# MegaShield_v0_6.net
KiCad netlist of a schematic drawn in EAGLE
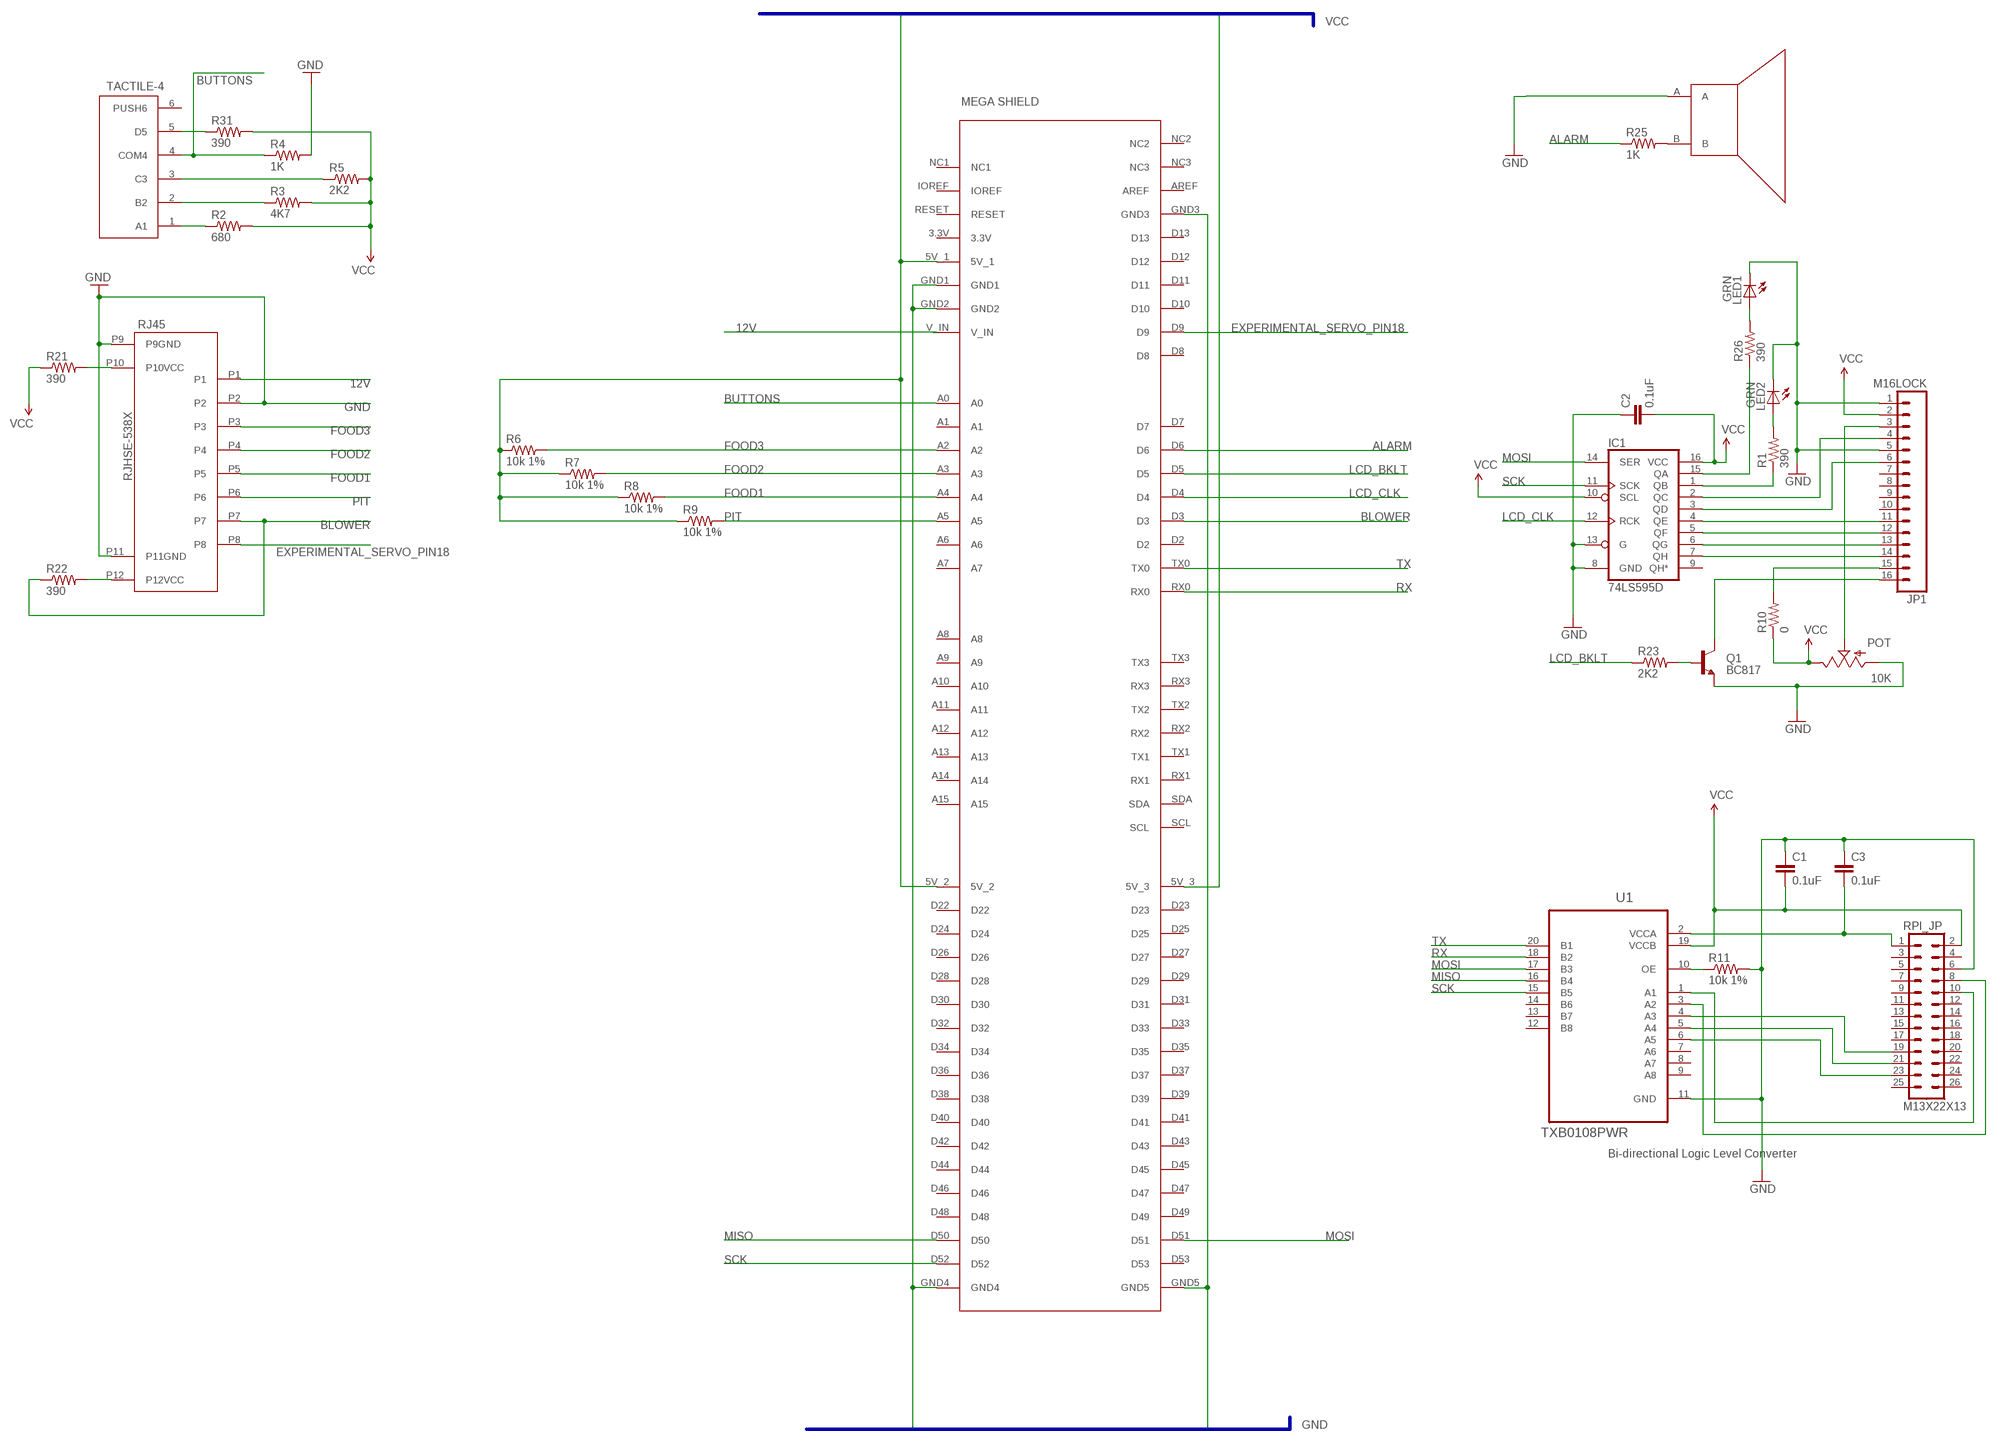
[diagram p0: schematic, sheet 1]

(export (version "E")
  (design (tool "Eeschema 10.0.6"))
  (components
    (comp (ref "C1")
      (value "0.1uF")
      (footprint "eagle-import:0805")
      (libsource (lib "eagle-import") (part "SparkFun-Passives_CAP0805"))
    )
    (comp (ref "C2")
      (value "0.1uF")
      (footprint "eagle-import:0805")
      (libsource (lib "eagle-import") (part "CAP0805"))
    )
    (comp (ref "C3")
      (value "0.1uF")
      (footprint "eagle-import:0805")
      (libsource (lib "eagle-import") (part "SparkFun-Passives_CAP0805"))
    )
    (comp (ref "IC1")
      (value "74LS595D")
      (footprint "eagle-import:SO16")
      (libsource (lib "eagle-import") (part "74595DLS"))
    )
    (comp (ref "JP1")
      (value "M16LOCK")
      (footprint "eagle-import:1X16_LOCK")
      (libsource (lib "eagle-import") (part "M16LOCK"))
    )
    (comp (ref "LED1")
      (value "GRN")
      (footprint "eagle-import:LED5MM")
      (libsource (lib "eagle-import") (part "LED5MM"))
    )
    (comp (ref "LED2")
      (value "GRN")
      (footprint "eagle-import:LED5MM")
      (libsource (lib "eagle-import") (part "LED5MM"))
    )
    (comp (ref "POT")
      (value "10K")
      (footprint "eagle-import:3362U")
      (libsource (lib "eagle-import") (part "POT100K_3362U"))
    )
    (comp (ref "Q1")
      (value "BC817")
      (footprint "eagle-import:SOT23")
      (libsource (lib "eagle-import") (part "TRANSISTOR_NPNSOT23"))
    )
    (comp (ref "R1")
      (value "390")
      (footprint "eagle-import:0805")
      (libsource (lib "eagle-import") (part "RESISTOR0805-RES"))
    )
    (comp (ref "R2")
      (value "680")
      (footprint "eagle-import:0805")
      (libsource (lib "eagle-import") (part "RESISTOR0805-RES"))
    )
    (comp (ref "R3")
      (value "4K7")
      (footprint "eagle-import:0805")
      (libsource (lib "eagle-import") (part "RESISTOR0805-RES"))
    )
    (comp (ref "R4")
      (value "1K")
      (footprint "eagle-import:0805")
      (libsource (lib "eagle-import") (part "RESISTOR0805-RES"))
    )
    (comp (ref "R5")
      (value "2K2")
      (footprint "eagle-import:0805")
      (libsource (lib "eagle-import") (part "RESISTOR0805-RES"))
    )
    (comp (ref "R6")
      (value "10k 1%")
      (footprint "eagle-import:0805")
      (libsource (lib "eagle-import") (part "RESISTOR0805-RES"))
    )
    (comp (ref "R7")
      (value "10k 1%")
      (footprint "eagle-import:0805")
      (libsource (lib "eagle-import") (part "RESISTOR0805-RES"))
    )
    (comp (ref "R8")
      (value "10k 1%")
      (footprint "eagle-import:0805")
      (libsource (lib "eagle-import") (part "RESISTOR0805-RES"))
    )
    (comp (ref "R9")
      (value "10k 1%")
      (footprint "eagle-import:0805")
      (libsource (lib "eagle-import") (part "RESISTOR0805-RES"))
    )
    (comp (ref "R10")
      (value "0")
      (footprint "eagle-import:0805")
      (libsource (lib "eagle-import") (part "RESISTOR0805-RES"))
    )
    (comp (ref "R11")
      (value "10k 1%")
      (footprint "eagle-import:0805")
      (libsource (lib "eagle-import") (part "RESISTOR0805-RES"))
    )
    (comp (ref "R21")
      (value "390")
      (footprint "eagle-import:0805")
      (libsource (lib "eagle-import") (part "RESISTOR0805-RES"))
    )
    (comp (ref "R22")
      (value "390")
      (footprint "eagle-import:0805")
      (libsource (lib "eagle-import") (part "RESISTOR0805-RES"))
    )
    (comp (ref "R23")
      (value "2K2")
      (footprint "eagle-import:0805")
      (libsource (lib "eagle-import") (part "RESISTOR0805-RES"))
    )
    (comp (ref "R25")
      (value "1K")
      (footprint "eagle-import:0805")
      (libsource (lib "eagle-import") (part "RESISTOR0805-RES"))
    )
    (comp (ref "R26")
      (value "390")
      (footprint "eagle-import:0805")
      (libsource (lib "eagle-import") (part "RESISTOR0805-RES"))
    )
    (comp (ref "R31")
      (value "390")
      (footprint "eagle-import:0805")
      (libsource (lib "eagle-import") (part "RESISTOR0805-RES"))
    )
    (comp (ref "RJHSE-538X")
      (value "RJHSE-338X")
      (footprint "eagle-import:RJHSE-538X")
      (description "RJ45")
      (fields (field (name "PART_NAME") "RJHSE-538X"))
      (libsource (lib "eagle-import") (part "RJHSE-338X"))
    )
    (comp (ref "RPI_JP")
      (value "M13X22X13")
      (footprint "eagle-import:2X13")
      (libsource (lib "eagle-import") (part "M13X22X13"))
    )
    (comp (ref "TACTILE-4")
      (value "SKQUAAA010")
      (footprint "eagle-import:SKQUAAA010")
      (description "TACTILE-4")
      (libsource (lib "eagle-import") (part "SKQUAAA010"))
    )
    (comp (ref "U$1")
      (value "MEGASHILED")
      (footprint "eagle-import:MEGASHIELD")
      (description "MEGA SHIELD")
      (libsource (lib "eagle-import") (part "MEGASHILED"))
    )
    (comp (ref "U$4")
      (value "PS1240P02BT")
      (footprint "eagle-import:PS1240P02BT")
      (libsource (lib "eagle-import") (part "PS1240P02BT"))
    )
    (comp (ref "U1")
      (value "TXB0108PWR")
      (footprint "eagle-import:SOP65P640X120-20N")
      (fields (field (name "DESCRIPT") " Bi-directional Logic Level Converter"))
      (libsource (lib "eagle-import") (part "TXB0108PWR"))
    )
  )
  (nets
    (net (code "1") (name "/12V") (class "Default")
      (node (ref "RJHSE-538X") (pin "P1") (pinfunction "P1_P1") (pintype "bidirectional"))
      (node (ref "U$1") (pin "V_IN") (pinfunction "V_IN_V_IN") (pintype "bidirectional"))
    )
    (net (code "2") (name "/ALARM") (class "Default")
      (node (ref "R25") (pin "1") (pinfunction "1_1") (pintype "passive"))
      (node (ref "U$1") (pin "D6") (pinfunction "D6_D6") (pintype "bidirectional"))
    )
    (net (code "3") (name "/BLOWER") (class "Default")
      (node (ref "R22") (pin "1") (pinfunction "1_1") (pintype "passive"))
      (node (ref "RJHSE-538X") (pin "P7") (pinfunction "P7_P7") (pintype "bidirectional"))
      (node (ref "U$1") (pin "D3") (pinfunction "D3_D3") (pintype "bidirectional"))
    )
    (net (code "4") (name "/BUTTONS") (class "Default")
      (node (ref "R4") (pin "1") (pinfunction "1_1") (pintype "passive"))
      (node (ref "TACTILE-4") (pin "4") (pinfunction "COM4_4") (pintype "bidirectional"))
      (node (ref "U$1") (pin "A0") (pinfunction "A0_A0") (pintype "bidirectional"))
    )
    (net (code "5") (name "/EXPERIMENTAL_SERVO_PIN18") (class "Default")
      (node (ref "RJHSE-538X") (pin "P8") (pinfunction "P8_P8") (pintype "bidirectional"))
      (node (ref "U$1") (pin "D9") (pinfunction "D9_D9") (pintype "bidirectional"))
    )
    (net (code "6") (name "/FOOD1") (class "Default")
      (node (ref "R8") (pin "2") (pinfunction "2_2") (pintype "passive"))
      (node (ref "RJHSE-538X") (pin "P5") (pinfunction "P5_P5") (pintype "bidirectional"))
      (node (ref "U$1") (pin "A4") (pinfunction "A4_A4") (pintype "bidirectional"))
    )
    (net (code "7") (name "/FOOD2") (class "Default")
      (node (ref "R7") (pin "2") (pinfunction "2_2") (pintype "passive"))
      (node (ref "RJHSE-538X") (pin "P4") (pinfunction "P4_P4") (pintype "bidirectional"))
      (node (ref "U$1") (pin "A3") (pinfunction "A3_A3") (pintype "bidirectional"))
    )
    (net (code "8") (name "/FOOD3") (class "Default")
      (node (ref "R6") (pin "2") (pinfunction "2_2") (pintype "passive"))
      (node (ref "RJHSE-538X") (pin "P3") (pinfunction "P3_P3") (pintype "bidirectional"))
      (node (ref "U$1") (pin "A2") (pinfunction "A2_A2") (pintype "bidirectional"))
    )
    (net (code "9") (name "/LCD_BKLT") (class "Default")
      (node (ref "R23") (pin "1") (pinfunction "1_1") (pintype "passive"))
      (node (ref "U$1") (pin "D5") (pinfunction "D5_D5") (pintype "bidirectional"))
    )
    (net (code "10") (name "/LCD_CLK") (class "Default")
      (node (ref "IC1") (pin "12") (pinfunction "RCK_12") (pintype "input"))
      (node (ref "U$1") (pin "D4") (pinfunction "D4_D4") (pintype "bidirectional"))
    )
    (net (code "11") (name "/MISO") (class "Default")
      (node (ref "U$1") (pin "D50") (pinfunction "D50_D50") (pintype "bidirectional"))
      (node (ref "U1") (pin "16") (pinfunction "B4_16") (pintype "bidirectional"))
    )
    (net (code "12") (name "/MOSI") (class "Default")
      (node (ref "IC1") (pin "14") (pinfunction "SER_14") (pintype "input"))
      (node (ref "U$1") (pin "D51") (pinfunction "D51_D51") (pintype "bidirectional"))
      (node (ref "U1") (pin "17") (pinfunction "B3_17") (pintype "bidirectional"))
    )
    (net (code "13") (name "/PIT") (class "Default")
      (node (ref "R9") (pin "2") (pinfunction "2_2") (pintype "passive"))
      (node (ref "RJHSE-538X") (pin "P6") (pinfunction "P6_P6") (pintype "bidirectional"))
      (node (ref "U$1") (pin "A5") (pinfunction "A5_A5") (pintype "bidirectional"))
    )
    (net (code "14") (name "/RX") (class "Default")
      (node (ref "U$1") (pin "RX0") (pinfunction "RX0_RX0") (pintype "bidirectional"))
      (node (ref "U1") (pin "18") (pinfunction "B2_18") (pintype "bidirectional"))
    )
    (net (code "15") (name "/SCK") (class "Default")
      (node (ref "IC1") (pin "11") (pinfunction "SCK_11") (pintype "input"))
      (node (ref "U$1") (pin "D52") (pinfunction "D52_D52") (pintype "bidirectional"))
      (node (ref "U1") (pin "15") (pinfunction "B5_15") (pintype "bidirectional"))
    )
    (net (code "16") (name "/TX") (class "Default")
      (node (ref "U$1") (pin "TX0") (pinfunction "TX0_TX0") (pintype "bidirectional"))
      (node (ref "U1") (pin "20") (pinfunction "B1_20") (pintype "bidirectional"))
    )
    (net (code "19") (name "GND") (class "Default")
      (node (ref "C1") (pin "1") (pinfunction "1_1") (pintype "passive"))
      (node (ref "C2") (pin "1") (pinfunction "1_1") (pintype "passive"))
      (node (ref "C3") (pin "1") (pinfunction "1_1") (pintype "passive"))
      (node (ref "IC1") (pin "13") (pinfunction "G_13") (pintype "input"))
      (node (ref "IC1") (pin "8") (pinfunction "GND_8") (pintype "power_in"))
      (node (ref "JP1") (pin "1") (pinfunction "1_1") (pintype "passive"))
      (node (ref "JP1") (pin "5") (pinfunction "5_5") (pintype "passive"))
      (node (ref "LED1") (pin "K") (pinfunction "C_K") (pintype "passive"))
      (node (ref "LED2") (pin "K") (pinfunction "C_K") (pintype "passive"))
      (node (ref "POT") (pin "P$3") (pinfunction "A_P$3") (pintype "passive"))
      (node (ref "Q1") (pin "2") (pinfunction "E_2") (pintype "passive"))
      (node (ref "R11") (pin "2") (pinfunction "2_2") (pintype "passive"))
      (node (ref "R4") (pin "2") (pinfunction "2_2") (pintype "passive"))
      (node (ref "RJHSE-538X") (pin "P11") (pinfunction "P11GND_P11") (pintype "bidirectional"))
      (node (ref "RJHSE-538X") (pin "P2") (pinfunction "P2_P2") (pintype "bidirectional"))
      (node (ref "RJHSE-538X") (pin "P9") (pinfunction "P9GND_P9") (pintype "bidirectional"))
      (node (ref "RPI_JP") (pin "6") (pinfunction "6_6") (pintype "passive"))
      (node (ref "U$1") (pin "GND1") (pinfunction "GND1_GND1") (pintype "bidirectional"))
      (node (ref "U$1") (pin "GND2") (pinfunction "GND2_GND2") (pintype "bidirectional"))
      (node (ref "U$1") (pin "GND3") (pinfunction "GND3_GND3") (pintype "bidirectional"))
      (node (ref "U$1") (pin "GND4") (pinfunction "GND4_GND4") (pintype "bidirectional"))
      (node (ref "U$1") (pin "GND5") (pinfunction "GND5_GND5") (pintype "bidirectional"))
      (node (ref "U$4") (pin "A") (pinfunction "A_A") (pintype "bidirectional"))
      (node (ref "U1") (pin "11") (pinfunction "GND_11") (pintype "passive"))
    )
    (net (code "20") (name "Net-(IC1-QA)") (class "Default")
      (node (ref "IC1") (pin "15") (pinfunction "QA_15") (pintype "tri_state"))
      (node (ref "R26") (pin "1") (pinfunction "1_1") (pintype "passive"))
    )
    (net (code "21") (name "Net-(IC1-QB)") (class "Default")
      (node (ref "IC1") (pin "1") (pinfunction "QB_1") (pintype "tri_state"))
      (node (ref "R1") (pin "1") (pinfunction "1_1") (pintype "passive"))
    )
    (net (code "22") (name "Net-(IC1-QC)") (class "Default")
      (node (ref "IC1") (pin "2") (pinfunction "QC_2") (pintype "tri_state"))
      (node (ref "JP1") (pin "4") (pinfunction "4_4") (pintype "passive"))
    )
    (net (code "23") (name "Net-(IC1-QD)") (class "Default")
      (node (ref "IC1") (pin "3") (pinfunction "QD_3") (pintype "tri_state"))
      (node (ref "JP1") (pin "6") (pinfunction "6_6") (pintype "passive"))
    )
    (net (code "24") (name "Net-(IC1-QE)") (class "Default")
      (node (ref "IC1") (pin "4") (pinfunction "QE_4") (pintype "tri_state"))
      (node (ref "JP1") (pin "11") (pinfunction "11_11") (pintype "passive"))
    )
    (net (code "25") (name "Net-(IC1-QF)") (class "Default")
      (node (ref "IC1") (pin "5") (pinfunction "QF_5") (pintype "tri_state"))
      (node (ref "JP1") (pin "12") (pinfunction "12_12") (pintype "passive"))
    )
    (net (code "26") (name "Net-(IC1-QG)") (class "Default")
      (node (ref "IC1") (pin "6") (pinfunction "QG_6") (pintype "tri_state"))
      (node (ref "JP1") (pin "13") (pinfunction "13_13") (pintype "passive"))
    )
    (net (code "27") (name "Net-(IC1-QH)") (class "Default")
      (node (ref "IC1") (pin "7") (pinfunction "QH_7") (pintype "tri_state"))
      (node (ref "JP1") (pin "14") (pinfunction "14_14") (pintype "passive"))
    )
    (net (code "28") (name "Net-(JP1-Pad15)") (class "Default")
      (node (ref "JP1") (pin "15") (pinfunction "15_15") (pintype "passive"))
      (node (ref "R10") (pin "2") (pinfunction "2_2") (pintype "passive"))
    )
    (net (code "29") (name "Net-(LED1-PadA)") (class "Default")
      (node (ref "LED1") (pin "A") (pinfunction "A_A") (pintype "passive"))
      (node (ref "R26") (pin "2") (pinfunction "2_2") (pintype "passive"))
    )
    (net (code "30") (name "Net-(LED2-PadA)") (class "Default")
      (node (ref "LED2") (pin "A") (pinfunction "A_A") (pintype "passive"))
      (node (ref "R1") (pin "2") (pinfunction "2_2") (pintype "passive"))
    )
    (net (code "31") (name "Net-(POT-S)") (class "Default")
      (node (ref "JP1") (pin "3") (pinfunction "3_3") (pintype "passive"))
      (node (ref "POT") (pin "P$2") (pinfunction "S_P$2") (pintype "passive"))
    )
    (net (code "32") (name "Net-(Q1-B)") (class "Default")
      (node (ref "Q1") (pin "1") (pinfunction "B_1") (pintype "passive"))
      (node (ref "R23") (pin "2") (pinfunction "2_2") (pintype "passive"))
    )
    (net (code "33") (name "Net-(Q1-C)") (class "Default")
      (node (ref "JP1") (pin "16") (pinfunction "16_16") (pintype "passive"))
      (node (ref "Q1") (pin "3") (pinfunction "C_3") (pintype "passive"))
    )
    (net (code "34") (name "Net-(R25-Pad2)") (class "Default")
      (node (ref "R25") (pin "2") (pinfunction "2_2") (pintype "passive"))
      (node (ref "U$4") (pin "B") (pinfunction "B_B") (pintype "bidirectional"))
    )
    (net (code "35") (name "Net-(RJHSE-538X-P10VCC)") (class "Default")
      (node (ref "R21") (pin "2") (pinfunction "2_2") (pintype "passive"))
      (node (ref "RJHSE-538X") (pin "P10") (pinfunction "P10VCC_P10") (pintype "bidirectional"))
    )
    (net (code "36") (name "Net-(RJHSE-538X-P12VCC)") (class "Default")
      (node (ref "R22") (pin "2") (pinfunction "2_2") (pintype "passive"))
      (node (ref "RJHSE-538X") (pin "P12") (pinfunction "P12VCC_P12") (pintype "bidirectional"))
    )
    (net (code "37") (name "Net-(TACTILE-4-A1)") (class "Default")
      (node (ref "R2") (pin "1") (pinfunction "1_1") (pintype "passive"))
      (node (ref "TACTILE-4") (pin "1") (pinfunction "A1_1") (pintype "bidirectional"))
    )
    (net (code "38") (name "Net-(TACTILE-4-B2)") (class "Default")
      (node (ref "R3") (pin "1") (pinfunction "1_1") (pintype "passive"))
      (node (ref "TACTILE-4") (pin "2") (pinfunction "B2_2") (pintype "bidirectional"))
    )
    (net (code "39") (name "Net-(TACTILE-4-C3)") (class "Default")
      (node (ref "R5") (pin "1") (pinfunction "1_1") (pintype "passive"))
      (node (ref "TACTILE-4") (pin "3") (pinfunction "C3_3") (pintype "bidirectional"))
    )
    (net (code "40") (name "Net-(TACTILE-4-D5)") (class "Default")
      (node (ref "R31") (pin "1") (pinfunction "1_1") (pintype "passive"))
      (node (ref "TACTILE-4") (pin "5") (pinfunction "D5_5") (pintype "bidirectional"))
    )
    (net (code "41") (name "Net-(U1-A1)") (class "Default")
      (node (ref "RPI_JP") (pin "10") (pinfunction "10_10") (pintype "passive"))
      (node (ref "U1") (pin "1") (pinfunction "A1_1") (pintype "bidirectional"))
    )
    (net (code "42") (name "Net-(U1-A2)") (class "Default")
      (node (ref "RPI_JP") (pin "8") (pinfunction "8_8") (pintype "passive"))
      (node (ref "U1") (pin "3") (pinfunction "A2_3") (pintype "bidirectional"))
    )
    (net (code "43") (name "Net-(U1-A3)") (class "Default")
      (node (ref "RPI_JP") (pin "19") (pinfunction "19_19") (pintype "passive"))
      (node (ref "U1") (pin "4") (pinfunction "A3_4") (pintype "bidirectional"))
    )
    (net (code "44") (name "Net-(U1-A4)") (class "Default")
      (node (ref "RPI_JP") (pin "21") (pinfunction "21_21") (pintype "passive"))
      (node (ref "U1") (pin "5") (pinfunction "A4_5") (pintype "bidirectional"))
    )
    (net (code "45") (name "Net-(U1-A5)") (class "Default")
      (node (ref "RPI_JP") (pin "23") (pinfunction "23_23") (pintype "passive"))
      (node (ref "U1") (pin "6") (pinfunction "A5_6") (pintype "bidirectional"))
    )
    (net (code "46") (name "Net-(U1-OE)") (class "Default")
      (node (ref "R11") (pin "1") (pinfunction "1_1") (pintype "passive"))
      (node (ref "U1") (pin "10") (pinfunction "OE_10") (pintype "input"))
    )
    (net (code "47") (name "Net-(U1-VCCA)") (class "Default")
      (node (ref "C3") (pin "2") (pinfunction "2_2") (pintype "passive"))
      (node (ref "RPI_JP") (pin "1") (pinfunction "1_1") (pintype "passive"))
      (node (ref "U1") (pin "2") (pinfunction "VCCA_2") (pintype "power_in"))
    )
    (net (code "48") (name "VCC") (class "Default")
      (node (ref "C1") (pin "2") (pinfunction "2_2") (pintype "passive"))
      (node (ref "C2") (pin "2") (pinfunction "2_2") (pintype "passive"))
      (node (ref "IC1") (pin "10") (pinfunction "SCL_10") (pintype "input"))
      (node (ref "IC1") (pin "16") (pinfunction "VCC_16") (pintype "power_in"))
      (node (ref "JP1") (pin "2") (pinfunction "2_2") (pintype "passive"))
      (node (ref "POT") (pin "P$1") (pinfunction "E_P$1") (pintype "passive"))
      (node (ref "R10") (pin "1") (pinfunction "1_1") (pintype "passive"))
      (node (ref "R2") (pin "2") (pinfunction "2_2") (pintype "passive"))
      (node (ref "R21") (pin "1") (pinfunction "1_1") (pintype "passive"))
      (node (ref "R3") (pin "2") (pinfunction "2_2") (pintype "passive"))
      (node (ref "R31") (pin "2") (pinfunction "2_2") (pintype "passive"))
      (node (ref "R5") (pin "2") (pinfunction "2_2") (pintype "passive"))
      (node (ref "R6") (pin "1") (pinfunction "1_1") (pintype "passive"))
      (node (ref "R7") (pin "1") (pinfunction "1_1") (pintype "passive"))
      (node (ref "R8") (pin "1") (pinfunction "1_1") (pintype "passive"))
      (node (ref "R9") (pin "1") (pinfunction "1_1") (pintype "passive"))
      (node (ref "RPI_JP") (pin "2") (pinfunction "2_2") (pintype "passive"))
      (node (ref "U$1") (pin "5V_1") (pinfunction "5V_1_5V_1") (pintype "bidirectional"))
      (node (ref "U$1") (pin "5V_2") (pinfunction "5V_2_5V_2") (pintype "bidirectional"))
      (node (ref "U$1") (pin "5V_3") (pinfunction "5V_3_5V_3") (pintype "bidirectional"))
      (node (ref "U1") (pin "19") (pinfunction "VCCB_19") (pintype "power_in"))
    )
    (net (code "49") (name "unconnected-(IC1-QH*-Pad9)") (class "Default")
      (node (ref "IC1") (pin "9") (pinfunction "QH*_9") (pintype "tri_state"))
    )
    (net (code "50") (name "unconnected-(JP1-Pad7)") (class "Default")
      (node (ref "JP1") (pin "7") (pinfunction "7_7") (pintype "passive"))
    )
    (net (code "51") (name "unconnected-(JP1-Pad8)") (class "Default")
      (node (ref "JP1") (pin "8") (pinfunction "8_8") (pintype "passive"))
    )
    (net (code "52") (name "unconnected-(JP1-Pad9)") (class "Default")
      (node (ref "JP1") (pin "9") (pinfunction "9_9") (pintype "passive"))
    )
    (net (code "53") (name "unconnected-(JP1-Pad10)") (class "Default")
      (node (ref "JP1") (pin "10") (pinfunction "10_10") (pintype "passive"))
    )
    (net (code "54") (name "unconnected-(RPI_JP-Pad3)") (class "Default")
      (node (ref "RPI_JP") (pin "3") (pinfunction "3_3") (pintype "passive"))
    )
    (net (code "55") (name "unconnected-(RPI_JP-Pad4)") (class "Default")
      (node (ref "RPI_JP") (pin "4") (pinfunction "4_4") (pintype "passive"))
    )
    (net (code "56") (name "unconnected-(RPI_JP-Pad5)") (class "Default")
      (node (ref "RPI_JP") (pin "5") (pinfunction "5_5") (pintype "passive"))
    )
    (net (code "57") (name "unconnected-(RPI_JP-Pad7)") (class "Default")
      (node (ref "RPI_JP") (pin "7") (pinfunction "7_7") (pintype "passive"))
    )
    (net (code "58") (name "unconnected-(RPI_JP-Pad9)") (class "Default")
      (node (ref "RPI_JP") (pin "9") (pinfunction "9_9") (pintype "passive"))
    )
    (net (code "59") (name "unconnected-(RPI_JP-Pad11)") (class "Default")
      (node (ref "RPI_JP") (pin "11") (pinfunction "11_11") (pintype "passive"))
    )
    (net (code "60") (name "unconnected-(RPI_JP-Pad12)") (class "Default")
      (node (ref "RPI_JP") (pin "12") (pinfunction "12_12") (pintype "passive"))
    )
    (net (code "61") (name "unconnected-(RPI_JP-Pad13)") (class "Default")
      (node (ref "RPI_JP") (pin "13") (pinfunction "13_13") (pintype "passive"))
    )
    (net (code "62") (name "unconnected-(RPI_JP-Pad14)") (class "Default")
      (node (ref "RPI_JP") (pin "14") (pinfunction "14_14") (pintype "passive"))
    )
    (net (code "63") (name "unconnected-(RPI_JP-Pad15)") (class "Default")
      (node (ref "RPI_JP") (pin "15") (pinfunction "15_15") (pintype "passive"))
    )
    (net (code "64") (name "unconnected-(RPI_JP-Pad16)") (class "Default")
      (node (ref "RPI_JP") (pin "16") (pinfunction "16_16") (pintype "passive"))
    )
    (net (code "65") (name "unconnected-(RPI_JP-Pad17)") (class "Default")
      (node (ref "RPI_JP") (pin "17") (pinfunction "17_17") (pintype "passive"))
    )
    (net (code "66") (name "unconnected-(RPI_JP-Pad18)") (class "Default")
      (node (ref "RPI_JP") (pin "18") (pinfunction "18_18") (pintype "passive"))
    )
    (net (code "67") (name "unconnected-(RPI_JP-Pad20)") (class "Default")
      (node (ref "RPI_JP") (pin "20") (pinfunction "20_20") (pintype "passive"))
    )
    (net (code "68") (name "unconnected-(RPI_JP-Pad22)") (class "Default")
      (node (ref "RPI_JP") (pin "22") (pinfunction "22_22") (pintype "passive"))
    )
    (net (code "69") (name "unconnected-(RPI_JP-Pad24)") (class "Default")
      (node (ref "RPI_JP") (pin "24") (pinfunction "24_24") (pintype "passive"))
    )
    (net (code "70") (name "unconnected-(RPI_JP-Pad25)") (class "Default")
      (node (ref "RPI_JP") (pin "25") (pinfunction "25_25") (pintype "passive"))
    )
    (net (code "71") (name "unconnected-(RPI_JP-Pad26)") (class "Default")
      (node (ref "RPI_JP") (pin "26") (pinfunction "26_26") (pintype "passive"))
    )
    (net (code "72") (name "unconnected-(TACTILE-4-PUSH6-Pad6)") (class "Default")
      (node (ref "TACTILE-4") (pin "6") (pinfunction "PUSH6_6") (pintype "bidirectional"))
    )
    (net (code "73") (name "unconnected-(U$1-Pad3.3V)") (class "Default")
      (node (ref "U$1") (pin "3.3V") (pinfunction "3.3V_3.3V") (pintype "bidirectional"))
    )
    (net (code "74") (name "unconnected-(U$1-PadA1)") (class "Default")
      (node (ref "U$1") (pin "A1") (pinfunction "A1_A1") (pintype "bidirectional"))
    )
    (net (code "75") (name "unconnected-(U$1-PadA6)") (class "Default")
      (node (ref "U$1") (pin "A6") (pinfunction "A6_A6") (pintype "bidirectional"))
    )
    (net (code "76") (name "unconnected-(U$1-PadA7)") (class "Default")
      (node (ref "U$1") (pin "A7") (pinfunction "A7_A7") (pintype "bidirectional"))
    )
    (net (code "77") (name "unconnected-(U$1-PadA8)") (class "Default")
      (node (ref "U$1") (pin "A8") (pinfunction "A8_A8") (pintype "bidirectional"))
    )
    (net (code "78") (name "unconnected-(U$1-PadA9)") (class "Default")
      (node (ref "U$1") (pin "A9") (pinfunction "A9_A9") (pintype "bidirectional"))
    )
    (net (code "79") (name "unconnected-(U$1-PadA10)") (class "Default")
      (node (ref "U$1") (pin "A10") (pinfunction "A10_A10") (pintype "bidirectional"))
    )
    (net (code "80") (name "unconnected-(U$1-PadA11)") (class "Default")
      (node (ref "U$1") (pin "A11") (pinfunction "A11_A11") (pintype "bidirectional"))
    )
    (net (code "81") (name "unconnected-(U$1-PadA12)") (class "Default")
      (node (ref "U$1") (pin "A12") (pinfunction "A12_A12") (pintype "bidirectional"))
    )
    (net (code "82") (name "unconnected-(U$1-PadA13)") (class "Default")
      (node (ref "U$1") (pin "A13") (pinfunction "A13_A13") (pintype "bidirectional"))
    )
    (net (code "83") (name "unconnected-(U$1-PadA14)") (class "Default")
      (node (ref "U$1") (pin "A14") (pinfunction "A14_A14") (pintype "bidirectional"))
    )
    (net (code "84") (name "unconnected-(U$1-PadA15)") (class "Default")
      (node (ref "U$1") (pin "A15") (pinfunction "A15_A15") (pintype "bidirectional"))
    )
    (net (code "85") (name "unconnected-(U$1-PadAREF)") (class "Default")
      (node (ref "U$1") (pin "AREF") (pinfunction "AREF_AREF") (pintype "bidirectional"))
    )
    (net (code "86") (name "unconnected-(U$1-PadD2)") (class "Default")
      (node (ref "U$1") (pin "D2") (pinfunction "D2_D2") (pintype "bidirectional"))
    )
    (net (code "87") (name "unconnected-(U$1-PadD7)") (class "Default")
      (node (ref "U$1") (pin "D7") (pinfunction "D7_D7") (pintype "bidirectional"))
    )
    (net (code "88") (name "unconnected-(U$1-PadD8)") (class "Default")
      (node (ref "U$1") (pin "D8") (pinfunction "D8_D8") (pintype "bidirectional"))
    )
    (net (code "89") (name "unconnected-(U$1-PadD10)") (class "Default")
      (node (ref "U$1") (pin "D10") (pinfunction "D10_D10") (pintype "bidirectional"))
    )
    (net (code "90") (name "unconnected-(U$1-PadD11)") (class "Default")
      (node (ref "U$1") (pin "D11") (pinfunction "D11_D11") (pintype "bidirectional"))
    )
    (net (code "91") (name "unconnected-(U$1-PadD12)") (class "Default")
      (node (ref "U$1") (pin "D12") (pinfunction "D12_D12") (pintype "bidirectional"))
    )
    (net (code "92") (name "unconnected-(U$1-PadD13)") (class "Default")
      (node (ref "U$1") (pin "D13") (pinfunction "D13_D13") (pintype "bidirectional"))
    )
    (net (code "93") (name "unconnected-(U$1-PadD22)") (class "Default")
      (node (ref "U$1") (pin "D22") (pinfunction "D22_D22") (pintype "bidirectional"))
    )
    (net (code "94") (name "unconnected-(U$1-PadD23)") (class "Default")
      (node (ref "U$1") (pin "D23") (pinfunction "D23_D23") (pintype "bidirectional"))
    )
    (net (code "95") (name "unconnected-(U$1-PadD24)") (class "Default")
      (node (ref "U$1") (pin "D24") (pinfunction "D24_D24") (pintype "bidirectional"))
    )
    (net (code "96") (name "unconnected-(U$1-PadD25)") (class "Default")
      (node (ref "U$1") (pin "D25") (pinfunction "D25_D25") (pintype "bidirectional"))
    )
    (net (code "97") (name "unconnected-(U$1-PadD26)") (class "Default")
      (node (ref "U$1") (pin "D26") (pinfunction "D26_D26") (pintype "bidirectional"))
    )
    (net (code "98") (name "unconnected-(U$1-PadD27)") (class "Default")
      (node (ref "U$1") (pin "D27") (pinfunction "D27_D27") (pintype "bidirectional"))
    )
    (net (code "99") (name "unconnected-(U$1-PadD28)") (class "Default")
      (node (ref "U$1") (pin "D28") (pinfunction "D28_D28") (pintype "bidirectional"))
    )
    (net (code "100") (name "unconnected-(U$1-PadD29)") (class "Default")
      (node (ref "U$1") (pin "D29") (pinfunction "D29_D29") (pintype "bidirectional"))
    )
    (net (code "101") (name "unconnected-(U$1-PadD30)") (class "Default")
      (node (ref "U$1") (pin "D30") (pinfunction "D30_D30") (pintype "bidirectional"))
    )
    (net (code "102") (name "unconnected-(U$1-PadD31)") (class "Default")
      (node (ref "U$1") (pin "D31") (pinfunction "D31_D31") (pintype "bidirectional"))
    )
    (net (code "103") (name "unconnected-(U$1-PadD32)") (class "Default")
      (node (ref "U$1") (pin "D32") (pinfunction "D32_D32") (pintype "bidirectional"))
    )
    (net (code "104") (name "unconnected-(U$1-PadD33)") (class "Default")
      (node (ref "U$1") (pin "D33") (pinfunction "D33_D33") (pintype "bidirectional"))
    )
    (net (code "105") (name "unconnected-(U$1-PadD34)") (class "Default")
      (node (ref "U$1") (pin "D34") (pinfunction "D34_D34") (pintype "bidirectional"))
    )
    (net (code "106") (name "unconnected-(U$1-PadD35)") (class "Default")
      (node (ref "U$1") (pin "D35") (pinfunction "D35_D35") (pintype "bidirectional"))
    )
    (net (code "107") (name "unconnected-(U$1-PadD36)") (class "Default")
      (node (ref "U$1") (pin "D36") (pinfunction "D36_D36") (pintype "bidirectional"))
    )
    (net (code "108") (name "unconnected-(U$1-PadD37)") (class "Default")
      (node (ref "U$1") (pin "D37") (pinfunction "D37_D37") (pintype "bidirectional"))
    )
    (net (code "109") (name "unconnected-(U$1-PadD38)") (class "Default")
      (node (ref "U$1") (pin "D38") (pinfunction "D38_D38") (pintype "bidirectional"))
    )
    (net (code "110") (name "unconnected-(U$1-PadD39)") (class "Default")
      (node (ref "U$1") (pin "D39") (pinfunction "D39_D39") (pintype "bidirectional"))
    )
    (net (code "111") (name "unconnected-(U$1-PadD40)") (class "Default")
      (node (ref "U$1") (pin "D40") (pinfunction "D40_D40") (pintype "bidirectional"))
    )
    (net (code "112") (name "unconnected-(U$1-PadD41)") (class "Default")
      (node (ref "U$1") (pin "D41") (pinfunction "D41_D41") (pintype "bidirectional"))
    )
    (net (code "113") (name "unconnected-(U$1-PadD42)") (class "Default")
      (node (ref "U$1") (pin "D42") (pinfunction "D42_D42") (pintype "bidirectional"))
    )
    (net (code "114") (name "unconnected-(U$1-PadD43)") (class "Default")
      (node (ref "U$1") (pin "D43") (pinfunction "D43_D43") (pintype "bidirectional"))
    )
    (net (code "115") (name "unconnected-(U$1-PadD44)") (class "Default")
      (node (ref "U$1") (pin "D44") (pinfunction "D44_D44") (pintype "bidirectional"))
    )
    (net (code "116") (name "unconnected-(U$1-PadD45)") (class "Default")
      (node (ref "U$1") (pin "D45") (pinfunction "D45_D45") (pintype "bidirectional"))
    )
    (net (code "117") (name "unconnected-(U$1-PadD46)") (class "Default")
      (node (ref "U$1") (pin "D46") (pinfunction "D46_D46") (pintype "bidirectional"))
    )
    (net (code "118") (name "unconnected-(U$1-PadD47)") (class "Default")
      (node (ref "U$1") (pin "D47") (pinfunction "D47_D47") (pintype "bidirectional"))
    )
    (net (code "119") (name "unconnected-(U$1-PadD48)") (class "Default")
      (node (ref "U$1") (pin "D48") (pinfunction "D48_D48") (pintype "bidirectional"))
    )
    (net (code "120") (name "unconnected-(U$1-PadD49)") (class "Default")
      (node (ref "U$1") (pin "D49") (pinfunction "D49_D49") (pintype "bidirectional"))
    )
    (net (code "121") (name "unconnected-(U$1-PadD53)") (class "Default")
      (node (ref "U$1") (pin "D53") (pinfunction "D53_D53") (pintype "bidirectional"))
    )
    (net (code "122") (name "unconnected-(U$1-PadIOREF)") (class "Default")
      (node (ref "U$1") (pin "IOREF") (pinfunction "IOREF_IOREF") (pintype "bidirectional"))
    )
    (net (code "123") (name "unconnected-(U$1-PadNC1)") (class "Default")
      (node (ref "U$1") (pin "NC1") (pinfunction "NC1_NC1") (pintype "bidirectional"))
    )
    (net (code "124") (name "unconnected-(U$1-PadNC2)") (class "Default")
      (node (ref "U$1") (pin "NC2") (pinfunction "NC2_NC2") (pintype "bidirectional"))
    )
    (net (code "125") (name "unconnected-(U$1-PadNC3)") (class "Default")
      (node (ref "U$1") (pin "NC3") (pinfunction "NC3_NC3") (pintype "bidirectional"))
    )
    (net (code "126") (name "unconnected-(U$1-PadRESET)") (class "Default")
      (node (ref "U$1") (pin "RESET") (pinfunction "RESET_RESET") (pintype "bidirectional"))
    )
    (net (code "127") (name "unconnected-(U$1-PadRX1)") (class "Default")
      (node (ref "U$1") (pin "RX1") (pinfunction "RX1_RX1") (pintype "bidirectional"))
    )
    (net (code "128") (name "unconnected-(U$1-PadRX2)") (class "Default")
      (node (ref "U$1") (pin "RX2") (pinfunction "RX2_RX2") (pintype "bidirectional"))
    )
    (net (code "129") (name "unconnected-(U$1-PadRX3)") (class "Default")
      (node (ref "U$1") (pin "RX3") (pinfunction "RX3_RX3") (pintype "bidirectional"))
    )
    (net (code "130") (name "unconnected-(U$1-PadSCL)") (class "Default")
      (node (ref "U$1") (pin "SCL") (pinfunction "SCL_SCL") (pintype "bidirectional"))
    )
    (net (code "131") (name "unconnected-(U$1-PadSDA)") (class "Default")
      (node (ref "U$1") (pin "SDA") (pinfunction "SDA_SDA") (pintype "bidirectional"))
    )
    (net (code "132") (name "unconnected-(U$1-PadTX1)") (class "Default")
      (node (ref "U$1") (pin "TX1") (pinfunction "TX1_TX1") (pintype "bidirectional"))
    )
    (net (code "133") (name "unconnected-(U$1-PadTX2)") (class "Default")
      (node (ref "U$1") (pin "TX2") (pinfunction "TX2_TX2") (pintype "bidirectional"))
    )
    (net (code "134") (name "unconnected-(U$1-PadTX3)") (class "Default")
      (node (ref "U$1") (pin "TX3") (pinfunction "TX3_TX3") (pintype "bidirectional"))
    )
    (net (code "135") (name "unconnected-(U1-A6-Pad7)") (class "Default")
      (node (ref "U1") (pin "7") (pinfunction "A6_7") (pintype "bidirectional"))
    )
    (net (code "136") (name "unconnected-(U1-A7-Pad8)") (class "Default")
      (node (ref "U1") (pin "8") (pinfunction "A7_8") (pintype "bidirectional"))
    )
    (net (code "137") (name "unconnected-(U1-A8-Pad9)") (class "Default")
      (node (ref "U1") (pin "9") (pinfunction "A8_9") (pintype "bidirectional"))
    )
    (net (code "138") (name "unconnected-(U1-B6-Pad14)") (class "Default")
      (node (ref "U1") (pin "14") (pinfunction "B6_14") (pintype "bidirectional"))
    )
    (net (code "139") (name "unconnected-(U1-B7-Pad13)") (class "Default")
      (node (ref "U1") (pin "13") (pinfunction "B7_13") (pintype "bidirectional"))
    )
    (net (code "140") (name "unconnected-(U1-B8-Pad12)") (class "Default")
      (node (ref "U1") (pin "12") (pinfunction "B8_12") (pintype "bidirectional"))
    )
  )
)
